# USB_suply_UART_bridge.net
KiCad netlist of a schematic drawn in Altium Designer
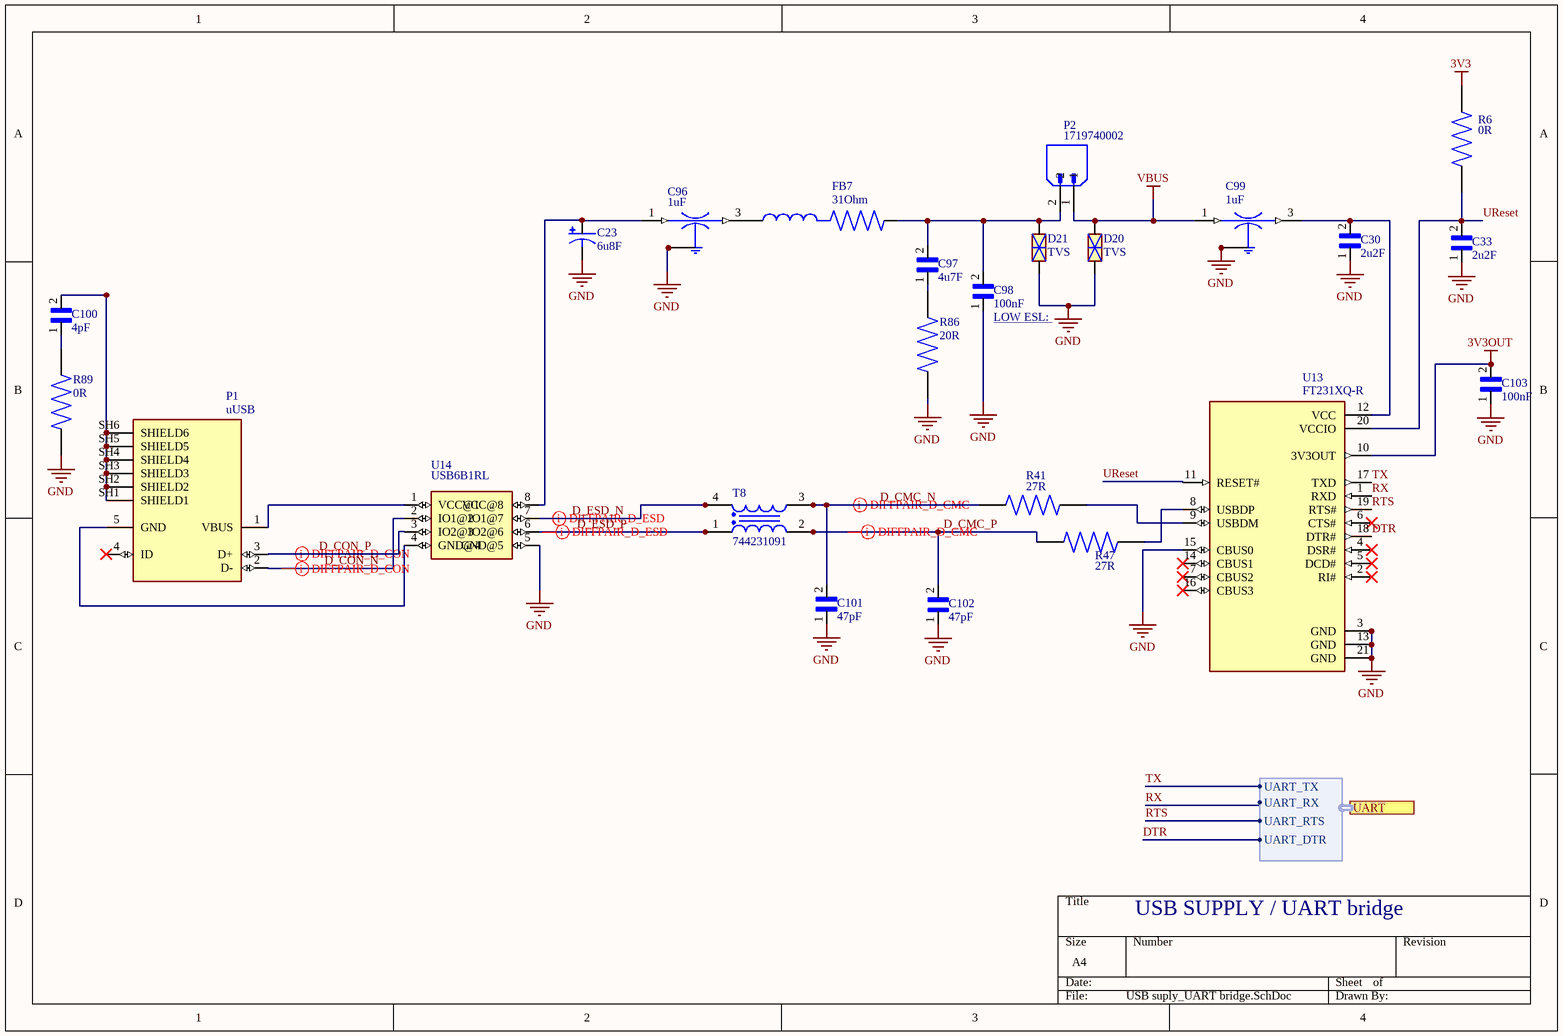
[diagram p0: USB suply_UART bridge.SchDoc]

(export (version "E")
  (design (tool "Eeschema 10.0.6"))
  (components
    (comp (ref "C23")
      (value "6u8F")
      (footprint "2917(POL)")
      (description "6.8 µF 16 V Aluminum - Polymer Capacitors 2917 (7343 Metric) 70mOhm 1000 Hrs @ 105°C")
      (fields (field (name "MF") "Murata") (field (name "MP") "ECASD41C685M070K00"))
      (libsource (lib "ECASD41C685M070K00") (part "ECASD41C685M070K00"))
    )
    (comp (ref "C30")
      (value "2u2F")
      (footprint "CAPC0603X35N")
      (description "SMD Capacitor X5R(EIA) with Capacitance: 2.2uF Tol. 20%. Rated Voltage: 6.3Vdc")
      (fields (field (name "MP") "GRM033R60J225ME15D"))
      (libsource (lib "GRM033R60J225ME15D") (part "GRM033R60J225ME15D"))
    )
    (comp (ref "C33")
      (value "2u2F")
      (footprint "CAPC0603X35N")
      (description "SMD Capacitor X5R(EIA) with Capacitance: 2.2uF Tol. 20%. Rated Voltage: 6.3Vdc")
      (fields (field (name "MP") "GRM033R60J225ME15D"))
      (libsource (lib "GRM033R60J225ME15D") (part "GRM033R60J225ME15D"))
    )
    (comp (ref "C96")
      (value "1uF")
      (footprint "FIL_NFM21PC105B1A3D")
      (description "SMD Capacitor with Capacitance: 1.0uF Tol. 20%. Rated Voltage: 10Vdc")
      (fields (field (name "MF") "Murata") (field (name "MP") "NFM21PC105B1A3D"))
      (libsource (lib "NFM21PC105B1A3D") (part "NFM21PC105B1A3D"))
    )
    (comp (ref "C97")
      (value "4u7F")
      (footprint "CAPC1608X100N")
      (description "SMD Capacitor X5R(EIA) with Capacitance: 4.7uF Tol. 10%. Rated Voltage: 10Vdc")
      (fields (field (name "MP") "GRM188R61A475KE15D") (field (name "MF") "Murata"))
      (libsource (lib "GRM188R61A475KE15D") (part "GRM188R61A475KE15D"))
    )
    (comp (ref "C98")
      (value "100nF")
      (footprint "CAPC0510X35N")
      (description "SMD Capacitor X6S(EIA) with Capacitance: 0.10uF Tol. 20%. Rated Voltage: 6.3Vdc")
      (fields (field (name "MF") "Murata") (field (name "MP") "LLL153C80J104ME01E"))
      (libsource (lib "LLL153C80J104ME01E") (part "LLL153C80J104ME01E"))
    )
    (comp (ref "C99")
      (value "1uF")
      (footprint "FIL_NFM21PC105B1A3D")
      (description "SMD Capacitor with Capacitance: 1.0uF Tol. 20%. Rated Voltage: 10Vdc")
      (fields (field (name "MF") "Murata") (field (name "MP") "NFM21PC105B1A3D"))
      (libsource (lib "NFM21PC105B1A3D") (part "NFM21PC105B1A3D"))
    )
    (comp (ref "C100")
      (value "4pF")
      (footprint "CAPC1005X55N")
      (description "Cap Ceramic 4pF 50V C0G 0.25pF SMD 0402 125Â°C Paper T/R")
      (fields (field (name "MP") "GRM1555C1H4R0CA01D"))
      (libsource (lib "GRM1555C1H4R0CA01D") (part "GRM1555C1H4R0CA01D"))
    )
    (comp (ref "C101")
      (value "47pF")
      (footprint "CAPC1005X55N")
      (description "CAP, MLCC, C0G, 47PF, 50V, 0402")
      (fields (field (name "MP") "GRM1555C1H470FA01D"))
      (libsource (lib "") (part "GRM1555C1H470FA01D_1"))
    )
    (comp (ref "C102")
      (value "47pF")
      (footprint "CAPC1005X55N")
      (description "CAP, MLCC, C0G, 47PF, 50V, 0402")
      (fields (field (name "MP") "GRM1555C1H470FA01D"))
      (libsource (lib "GRM1555C1H470FA01D") (part "GRM1555C1H470FA01D"))
    )
    (comp (ref "C103")
      (value "100nF")
      (footprint "CAPC0603X33N")
      (description "SMD capacitor X6S(EIA) with capacitance 0.10uF Tol.10%. Rated voltage 6.3Vdc 105C")
      (fields (field (name "MF") "Murata Electronics") (field (name "MP") "GRM033C80J104KE15D"))
      (libsource (lib "GRM033C80J104KE15D") (part "GRM033C80J104KE15D"))
    )
    (comp (ref "D20")
      (value "TVS")
      (footprint "ST0201")
      (description "17V Clamp 1A (8/20Âµs) Ipp Tvs Diode Surface Mount ST0201")
      (fields (field (name "MF") "STMicroelectronics") (field (name "MP") "ESDAXLC6-1BU2"))
      (libsource (lib "ESDAXLC6-1BU2") (part "ESDAXLC6-1BU2"))
    )
    (comp (ref "D21")
      (value "TVS")
      (footprint "ST0201")
      (description "17V Clamp 1A (8/20Âµs) Ipp Tvs Diode Surface Mount ST0201")
      (fields (field (name "MF") "STMicroelectronics") (field (name "MP") "ESDAXLC6-1BU2"))
      (libsource (lib "ESDAXLC6-1BU2") (part "ESDAXLC6-1BU2"))
    )
    (comp (ref "FB7")
      (value "31Ohm")
      (footprint "FIL_NFZ32BW310HN11L")
      (description "31 Ohms @ 1MHz 1 Ferrite Bead 2-SMD, Flat Lead 1.2A 186mOhm")
      (fields (field (name "MP") "NFZ32BW310HN11L") (field (name "MF") "Murata"))
      (libsource (lib "NFZ32BW310HN11L") (part "NFZ32BW310HN11L"))
    )
    (comp (ref "P1")
      (value "uUSB")
      (footprint "MOLEX_1050170001")
      (description "USB - micro B USB 2.0 Receptacle Connector 5 Position Surface Mount, Right Angle; Through Hole")
      (fields (field (name "MF") "Molex") (field (name "MP") "1050170001"))
      (libsource (lib "1050170001") (part "1050170001"))
    )
    (comp (ref "P2")
      (value "1719740002")
      (footprint "MOLEX_1719740002")
      (libsource (lib "1719740002") (part "1719740002"))
    )
    (comp (ref "R6")
      (value "0R")
      (footprint "RESC1005X37N")
      (fields (field (name "MF") "{'manufacturer': u'YAGEO'}") (field (name "MP") "RC0402JR-070RL"))
      (libsource (lib "RC0402JR-070RL") (part "RC0402JR-070RL"))
    )
    (comp (ref "R41")
      (value "27R")
      (footprint "RESC1005X40N")
      (description "Surface Mount Thick Film Resistor, RC Series, 27 ohm, 63 mW, - 1%, 50 V, 0402 [1005 Metric]")
      (fields (field (name "MF") "Yageo") (field (name "DIGI-KEY_PART_NUMBER") "YAG3086CT-ND"))
      (libsource (lib "RC0402FR-0727RL") (part "RC0402FR-0727RL"))
    )
    (comp (ref "R47")
      (value "27R")
      (footprint "RESC1005X40N")
      (description "Surface Mount Thick Film Resistor, RC Series, 27 ohm, 63 mW, - 1%, 50 V, 0402 [1005 Metric]")
      (fields (field (name "MF") "Yageo") (field (name "DIGI-KEY_PART_NUMBER") "YAG3086CT-ND"))
      (libsource (lib "RC0402FR-0727RL") (part "RC0402FR-0727RL"))
    )
    (comp (ref "R86")
      (value "20R")
      (footprint "RESC1005X40N")
      (description "20 Ohms ±5% 0.063W, 1/16W Chip Resistor 0402 (1005 Metric) Moisture Resistant Thick Film")
      (fields (field (name "MF") "Yageo") (field (name "MP") "RC0402JR-0720RL"))
      (libsource (lib "RC0402JR-0720RL") (part "RC0402JR-0720RL"))
    )
    (comp (ref "R89")
      (value "0R")
      (footprint "RESC1005X37N")
      (fields (field (name "MF") "{'manufacturer': u'YAGEO'}") (field (name "MP") "RC0402JR-070RL"))
      (libsource (lib "RC0402JR-070RL") (part "RC0402JR-070RL"))
    )
    (comp (ref "T8")
      (value "744231091")
      (footprint "WE-CNSW_0805")
      (fields (field (name "TOLERANCE") "25%"))
      (libsource (lib "Altium Content Vault") (part "WE-CNSW"))
    )
    (comp (ref "U13")
      (value "FT231XQ-R")
      (footprint "QFN50P400X400X80-21N")
      (description "USB2.0 Full Speed IC offers a compact bridge to full handshake UART Interface")
      (libsource (lib "FT231XQ-R") (part "FT231XQ-R"))
    )
    (comp (ref "U14")
      (value "USB6B1RL")
      (footprint "SOIC8")
      (description "- Clamp - Ipp Tvs Diode Surface Mount 8-SOIC")
      (fields (field (name "MF") "STMicroelectronics"))
      (libsource (lib "USB6B1RL") (part "USB6B1RL"))
    )
  )
  (nets
    (net (code "2") (name "/DTR") (class "Default")
      (node (ref "U13") (pin "18") (pinfunction "DTR#_18") (pintype "output"))
    )
    (net (code "3") (name "/D_CMC_N") (class "Default")
      (node (ref "C101") (pin "2") (pinfunction "2_2") (pintype "passive"))
      (node (ref "R41") (pin "1") (pinfunction "1_1") (pintype "passive"))
      (node (ref "T8") (pin "3") (pinfunction "3_3") (pintype "passive"))
    )
    (net (code "4") (name "/D_CMC_P") (class "Default")
      (node (ref "C102") (pin "2") (pinfunction "2_2") (pintype "passive"))
      (node (ref "R47") (pin "1") (pinfunction "1_1") (pintype "passive"))
      (node (ref "T8") (pin "2") (pinfunction "2_2") (pintype "passive"))
    )
    (net (code "5") (name "/D_CON_N") (class "Default")
      (node (ref "P1") (pin "2") (pinfunction "D-_2") (pintype "bidirectional"))
      (node (ref "U14") (pin "2") (pinfunction "IO1@2_2") (pintype "bidirectional"))
    )
    (net (code "6") (name "/D_CON_P") (class "Default")
      (node (ref "P1") (pin "3") (pinfunction "D+_3") (pintype "bidirectional"))
      (node (ref "U14") (pin "3") (pinfunction "IO2@3_3") (pintype "bidirectional"))
    )
    (net (code "7") (name "/D_ESD_N") (class "Default")
      (node (ref "T8") (pin "4") (pinfunction "4_4") (pintype "passive"))
      (node (ref "U14") (pin "7") (pinfunction "IO1@7_7") (pintype "bidirectional"))
    )
    (net (code "8") (name "/D_ESD_P") (class "Default")
      (node (ref "T8") (pin "1") (pinfunction "1_1") (pintype "passive"))
      (node (ref "U14") (pin "6") (pinfunction "IO2@6_6") (pintype "bidirectional"))
    )
    (net (code "9") (name "/RTS") (class "Default")
      (node (ref "U13") (pin "19") (pinfunction "RTS#_19") (pintype "output"))
    )
    (net (code "10") (name "/RX") (class "Default")
      (node (ref "U13") (pin "1") (pinfunction "RXD_1") (pintype "input"))
    )
    (net (code "11") (name "/TX") (class "Default")
      (node (ref "U13") (pin "17") (pinfunction "TXD_17") (pintype "output"))
    )
    (net (code "12") (name "/UReset") (class "Default")
      (node (ref "C33") (pin "2") (pinfunction "2_2") (pintype "passive"))
      (node (ref "R6") (pin "1") (pinfunction "1_1") (pintype "passive"))
      (node (ref "U13") (pin "11") (pinfunction "RESET#_11") (pintype "input"))
      (node (ref "U13") (pin "20") (pinfunction "VCCIO_20") (pintype "power_in"))
    )
    (net (code "14") (name "3V3") (class "Default")
      (node (ref "R6") (pin "2") (pinfunction "2_2") (pintype "passive"))
    )
    (net (code "15") (name "3V3OUT") (class "Default")
      (node (ref "C103") (pin "2") (pinfunction "2_2") (pintype "passive"))
      (node (ref "U13") (pin "10") (pinfunction "3V3OUT_10") (pintype "output"))
    )
    (net (code "16") (name "GND") (class "Default")
      (node (ref "C101") (pin "1") (pinfunction "1_1") (pintype "passive"))
      (node (ref "C102") (pin "1") (pinfunction "1_1") (pintype "passive"))
      (node (ref "C103") (pin "1") (pinfunction "1_1") (pintype "passive"))
      (node (ref "C23") (pin "2") (pinfunction "NEG_2") (pintype "passive"))
      (node (ref "C30") (pin "1") (pinfunction "1_1") (pintype "passive"))
      (node (ref "C33") (pin "1") (pinfunction "1_1") (pintype "passive"))
      (node (ref "C96") (pin "2") (pinfunction "GND_2") (pintype "power_in"))
      (node (ref "C96") (pin "2_1") (pinfunction "GND_2_1") (pintype "power_in"))
      (node (ref "C96") (pin "2_2") (pinfunction "GND_2_2") (pintype "power_in"))
      (node (ref "C96") (pin "2_3") (pinfunction "GND_2_3") (pintype "power_in"))
      (node (ref "C96") (pin "2_4") (pinfunction "GND_2_4") (pintype "power_in"))
      (node (ref "C98") (pin "1") (pinfunction "1_1") (pintype "passive"))
      (node (ref "C99") (pin "2") (pinfunction "GND_2") (pintype "power_in"))
      (node (ref "C99") (pin "2_1") (pinfunction "GND_2_1") (pintype "power_in"))
      (node (ref "C99") (pin "2_2") (pinfunction "GND_2_2") (pintype "power_in"))
      (node (ref "C99") (pin "2_3") (pinfunction "GND_2_3") (pintype "power_in"))
      (node (ref "C99") (pin "2_4") (pinfunction "GND_2_4") (pintype "power_in"))
      (node (ref "D20") (pin "1") (pinfunction "1_1") (pintype "passive"))
      (node (ref "D21") (pin "1") (pinfunction "1_1") (pintype "passive"))
      (node (ref "R86") (pin "1") (pinfunction "1_1") (pintype "passive"))
      (node (ref "R89") (pin "1") (pinfunction "1_1") (pintype "passive"))
      (node (ref "U13") (pin "13") (pinfunction "GND_13") (pintype "power_in"))
      (node (ref "U13") (pin "15") (pinfunction "CBUS0_15") (pintype "bidirectional"))
      (node (ref "U13") (pin "21") (pinfunction "GND_21") (pintype "power_in"))
      (node (ref "U13") (pin "3") (pinfunction "GND_3") (pintype "power_in"))
      (node (ref "U14") (pin "5") (pinfunction "GND@5_5") (pintype "bidirectional"))
    )
    (net (code "17") (name "Net-(C23-POS)") (class "Default")
      (node (ref "C23") (pin "1") (pinfunction "POS_1") (pintype "passive"))
      (node (ref "C96") (pin "1") (pinfunction "IN_1") (pintype "input"))
      (node (ref "U14") (pin "8") (pinfunction "VCC@8_8") (pintype "bidirectional"))
    )
    (net (code "18") (name "Net-(C96-OUT)") (class "Default")
      (node (ref "C96") (pin "3") (pinfunction "OUT_3") (pintype "output"))
      (node (ref "FB7") (pin "1") (pinfunction "1_1") (pintype "passive"))
    )
    (net (code "19") (name "Net-(C97-Pad1)") (class "Default")
      (node (ref "C97") (pin "1") (pinfunction "1_1") (pintype "passive"))
      (node (ref "R86") (pin "2") (pinfunction "2_2") (pintype "passive"))
    )
    (net (code "20") (name "Net-(C97-Pad2)") (class "Default")
      (node (ref "C97") (pin "2") (pinfunction "2_2") (pintype "passive"))
      (node (ref "C98") (pin "2") (pinfunction "2_2") (pintype "passive"))
      (node (ref "D21") (pin "2") (pinfunction "2_2") (pintype "passive"))
      (node (ref "FB7") (pin "2") (pinfunction "2_2") (pintype "passive"))
      (node (ref "P2") (pin "2") (pinfunction "2_2") (pintype "passive"))
    )
    (net (code "21") (name "Net-(C99-OUT)") (class "Default")
      (node (ref "C30") (pin "2") (pinfunction "2_2") (pintype "passive"))
      (node (ref "C99") (pin "3") (pinfunction "OUT_3") (pintype "output"))
      (node (ref "U13") (pin "12") (pinfunction "VCC_12") (pintype "power_in"))
    )
    (net (code "22") (name "Net-(C100-Pad1)") (class "Default")
      (node (ref "C100") (pin "1") (pinfunction "1_1") (pintype "passive"))
      (node (ref "R89") (pin "2") (pinfunction "2_2") (pintype "passive"))
    )
    (net (code "23") (name "Net-(P1-GND)") (class "Default")
      (node (ref "P1") (pin "5") (pinfunction "GND_5") (pintype "power_in"))
      (node (ref "U14") (pin "4") (pinfunction "GND@4_4") (pintype "bidirectional"))
    )
    (net (code "24") (name "Net-(P1-SHIELD1)") (class "Default")
      (node (ref "C100") (pin "2") (pinfunction "2_2") (pintype "passive"))
      (node (ref "P1") (pin "SH1") (pinfunction "SHIELD1_SH1") (pintype "passive"))
      (node (ref "P1") (pin "SH2") (pinfunction "SHIELD2_SH2") (pintype "passive"))
      (node (ref "P1") (pin "SH3") (pinfunction "SHIELD3_SH3") (pintype "passive"))
      (node (ref "P1") (pin "SH4") (pinfunction "SHIELD4_SH4") (pintype "passive"))
      (node (ref "P1") (pin "SH5") (pinfunction "SHIELD5_SH5") (pintype "passive"))
      (node (ref "P1") (pin "SH6") (pinfunction "SHIELD6_SH6") (pintype "passive"))
    )
    (net (code "25") (name "Net-(P1-VBUS)") (class "Default")
      (node (ref "P1") (pin "1") (pinfunction "VBUS_1") (pintype "power_in"))
      (node (ref "U14") (pin "1") (pinfunction "VCC@1_1") (pintype "bidirectional"))
    )
    (net (code "26") (name "Net-(U13-USBDM)") (class "Default")
      (node (ref "R41") (pin "2") (pinfunction "2_2") (pintype "passive"))
      (node (ref "U13") (pin "9") (pinfunction "USBDM_9") (pintype "bidirectional"))
    )
    (net (code "27") (name "Net-(U13-USBDP)") (class "Default")
      (node (ref "R47") (pin "2") (pinfunction "2_2") (pintype "passive"))
      (node (ref "U13") (pin "8") (pinfunction "USBDP_8") (pintype "bidirectional"))
    )
    (net (code "28") (name "VBUS") (class "Default")
      (node (ref "C99") (pin "1") (pinfunction "IN_1") (pintype "input"))
      (node (ref "D20") (pin "2") (pinfunction "2_2") (pintype "passive"))
      (node (ref "P2") (pin "1") (pinfunction "1_1") (pintype "passive"))
    )
    (net (code "29") (name "unconnected-(P1-ID-Pad4)") (class "Default")
      (node (ref "P1") (pin "4") (pinfunction "ID_4") (pintype "bidirectional+no_connect"))
    )
    (net (code "30") (name "unconnected-(U13-CBUS1-Pad14)") (class "Default")
      (node (ref "U13") (pin "14") (pinfunction "CBUS1_14") (pintype "bidirectional+no_connect"))
    )
    (net (code "31") (name "unconnected-(U13-CBUS2-Pad7)") (class "Default")
      (node (ref "U13") (pin "7") (pinfunction "CBUS2_7") (pintype "bidirectional+no_connect"))
    )
    (net (code "32") (name "unconnected-(U13-CBUS3-Pad16)") (class "Default")
      (node (ref "U13") (pin "16") (pinfunction "CBUS3_16") (pintype "bidirectional+no_connect"))
    )
    (net (code "33") (name "unconnected-(U13-CTS#-Pad6)") (class "Default")
      (node (ref "U13") (pin "6") (pinfunction "CTS#_6") (pintype "input+no_connect"))
    )
    (net (code "34") (name "unconnected-(U13-DCD#-Pad5)") (class "Default")
      (node (ref "U13") (pin "5") (pinfunction "DCD#_5") (pintype "input+no_connect"))
    )
    (net (code "35") (name "unconnected-(U13-DSR#-Pad4)") (class "Default")
      (node (ref "U13") (pin "4") (pinfunction "DSR#_4") (pintype "input+no_connect"))
    )
    (net (code "36") (name "unconnected-(U13-RI#-Pad2)") (class "Default")
      (node (ref "U13") (pin "2") (pinfunction "RI#_2") (pintype "input+no_connect"))
    )
  )
)
